# Thermal_imager_Down.net
KiCad netlist of a schematic drawn in Altium Designer
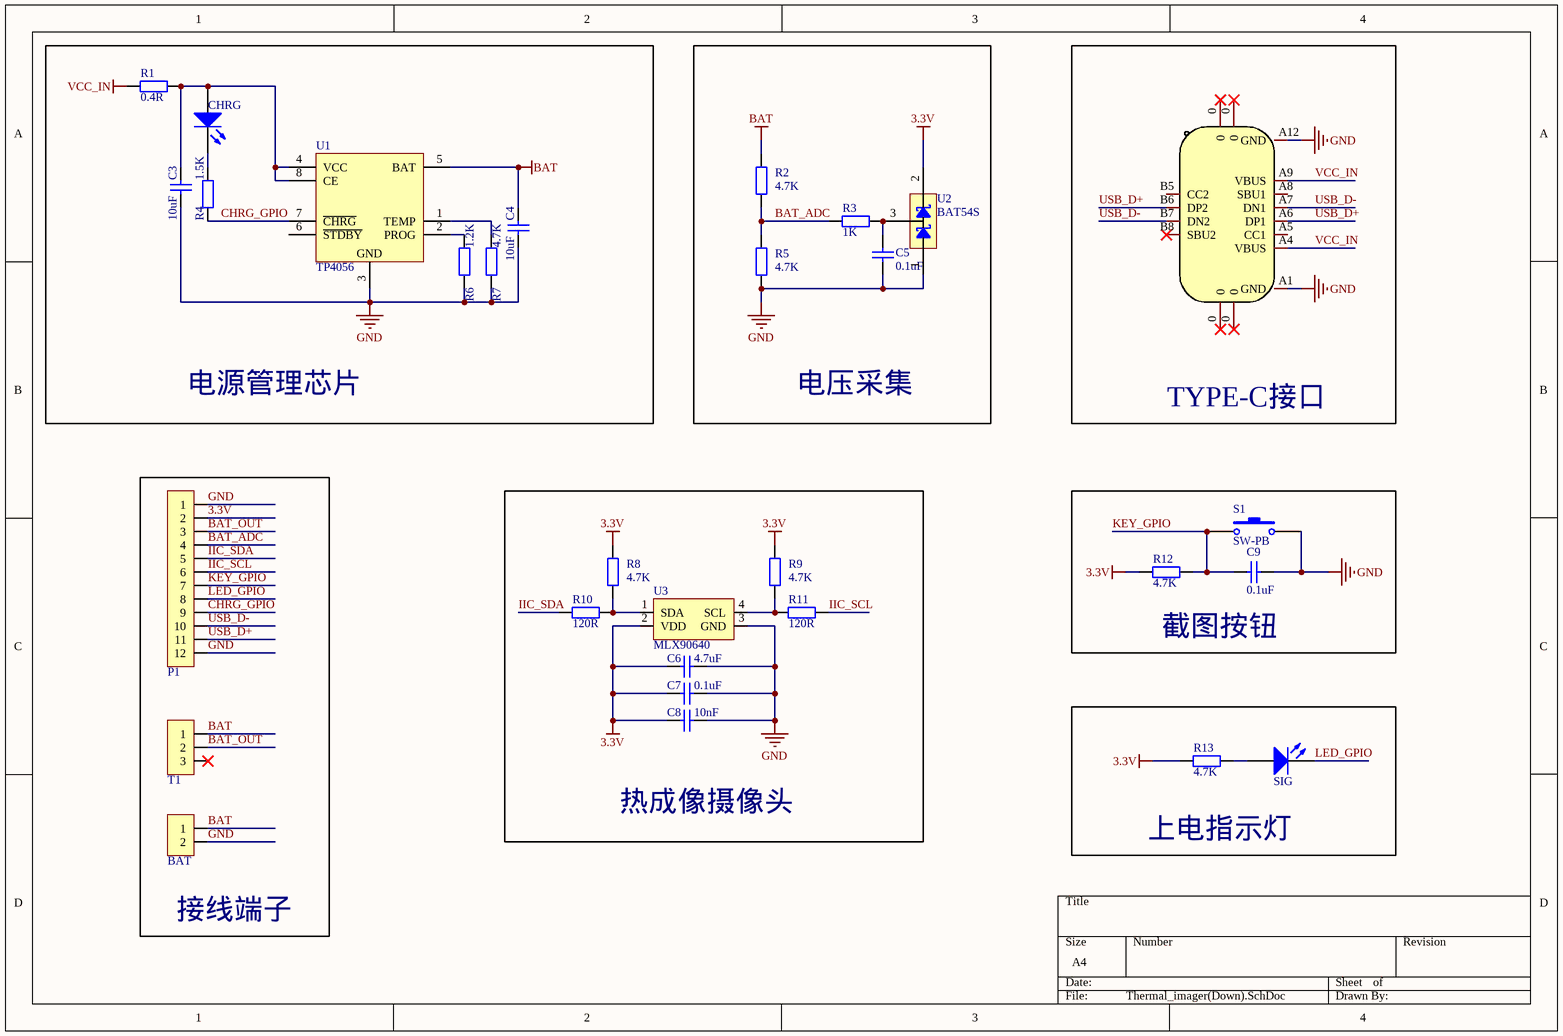
[diagram p0: Thermal_imager(Down).SchDoc]

(export (version "E")
  (design (tool "Eeschema 10.0.6"))
  (components
    (comp (ref "BAT")
      (value "Header 2*1")
      (footprint "COM_T_2.0_2P")
      (description "接插件")
      (fields (field (name "PUBLISHER") "Altium Limited"))
      (libsource (lib "Connect") (part "Header 2*1"))
    )
    (comp (ref "C3")
      (value "10uF")
      (footprint "LC-1206_C")
      (description "无极性电容")
      (fields (field (name "PUBLISHER") "Altium Limited"))
      (libsource (lib "Fszhang") (part "Cap"))
    )
    (comp (ref "C4")
      (value "10uF")
      (footprint "LC-1206_C")
      (description "无极性电容")
      (fields (field (name "PUBLISHER") "Altium Limited"))
      (libsource (lib "Fszhang") (part "Cap"))
    )
    (comp (ref "C5")
      (value "0.1uF")
      (footprint "LC-0603_C")
      (description "无极性电容")
      (fields (field (name "PUBLISHER") "Altium Limited"))
      (libsource (lib "Fszhang") (part "Cap"))
    )
    (comp (ref "C6")
      (value "4.7uF")
      (footprint "LC-0603_C")
      (description "无极性电容")
      (fields (field (name "PUBLISHER") "Altium Limited"))
      (libsource (lib "Fszhang") (part "Cap"))
    )
    (comp (ref "C7")
      (value "0.1uF")
      (footprint "LC-0603_C")
      (description "无极性电容")
      (fields (field (name "PUBLISHER") "Altium Limited"))
      (libsource (lib "Fszhang") (part "Cap"))
    )
    (comp (ref "C8")
      (value "10nF")
      (footprint "LC-0603_C")
      (description "无极性电容")
      (fields (field (name "PUBLISHER") "Altium Limited"))
      (libsource (lib "Fszhang") (part "Cap"))
    )
    (comp (ref "C9")
      (value "0.1uF")
      (footprint "LC-0603_C")
      (description "无极性电容")
      (fields (field (name "Comment") "Cap") (field (name "PUBLISHER") "Altium Limited"))
      (libsource (lib "Fszhang") (part "Cap"))
    )
    (comp (ref "CHRG")
      (value "LED0")
      (footprint "LC-0603_LED_S1")
      (description "发光二极管")
      (fields (field (name "PUBLISHER") "Altium Limited"))
      (libsource (lib "Fszhang") (part "LED0"))
    )
    (comp (ref "P1")
      (value "Header 12*1")
      (footprint "HDR12X1_A-1.27mm")
      (description "接插件")
      (fields (field (name "PUBLISHER") "Altium Limited"))
      (libsource (lib "Connect") (part "Header 12*1"))
    )
    (comp (ref "R1")
      (value "0.4R")
      (footprint "LC-1206_R")
      (description "贴片电阻")
      (fields (field (name "PUBLISHER") "Altium Limited"))
      (libsource (lib "") (part "=VALUE_1"))
    )
    (comp (ref "R2")
      (value "4.7K")
      (footprint "LC-0603_R")
      (description "贴片电阻")
      (fields (field (name "PUBLISHER") "Altium Limited"))
      (libsource (lib "Fszhang") (part "=VALUE"))
    )
    (comp (ref "R3")
      (value "1K")
      (footprint "LC-0603_R")
      (description "贴片电阻")
      (fields (field (name "PUBLISHER") "Altium Limited"))
      (libsource (lib "Fszhang") (part "Res1"))
    )
    (comp (ref "R4")
      (value "1.5K")
      (footprint "LC-0603_R")
      (description "贴片电阻")
      (fields (field (name "PUBLISHER") "Altium Limited"))
      (libsource (lib "Fszhang") (part "=VALUE"))
    )
    (comp (ref "R5")
      (value "4.7K")
      (footprint "LC-0603_R")
      (description "贴片电阻")
      (fields (field (name "PUBLISHER") "Altium Limited"))
      (libsource (lib "Fszhang") (part "=VALUE"))
    )
    (comp (ref "R6")
      (value "1.2K")
      (footprint "LC-0603_R")
      (description "贴片电阻")
      (fields (field (name "PUBLISHER") "Altium Limited"))
      (libsource (lib "Fszhang") (part "=VALUE"))
    )
    (comp (ref "R7")
      (value "4.7K")
      (footprint "LC-0603_R")
      (description "贴片电阻")
      (fields (field (name "PUBLISHER") "Altium Limited"))
      (libsource (lib "Fszhang") (part "=VALUE"))
    )
    (comp (ref "R8")
      (value "4.7K")
      (footprint "LC-0603_R")
      (description "贴片电阻")
      (fields (field (name "PUBLISHER") "Altium Limited"))
      (libsource (lib "Fszhang") (part "=VALUE"))
    )
    (comp (ref "R9")
      (value "4.7K")
      (footprint "LC-0603_R")
      (description "贴片电阻")
      (fields (field (name "PUBLISHER") "Altium Limited"))
      (libsource (lib "Fszhang") (part "=VALUE"))
    )
    (comp (ref "R10")
      (value "120R")
      (footprint "LC-0603_R")
      (description "贴片电阻")
      (fields (field (name "PUBLISHER") "Altium Limited"))
      (libsource (lib "") (part "=VALUE_2"))
    )
    (comp (ref "R11")
      (value "120R")
      (footprint "LC-0603_R")
      (description "贴片电阻")
      (fields (field (name "PUBLISHER") "Altium Limited"))
      (libsource (lib "") (part "=VALUE_2"))
    )
    (comp (ref "R12")
      (value "4.7K")
      (footprint "LC-0603_R")
      (description "贴片电阻")
      (fields (field (name "Comment") "Res1") (field (name "PUBLISHER") "Altium Limited"))
      (libsource (lib "Fszhang") (part "Res1"))
    )
    (comp (ref "R13")
      (value "4.7K")
      (footprint "LC-0603_R")
      (description "贴片电阻")
      (fields (field (name "Comment") "Res1") (field (name "PUBLISHER") "Altium Limited"))
      (libsource (lib "Fszhang") (part "Res1"))
    )
    (comp (ref "S1")
      (value "SW-PB")
      (footprint "KEY_3*6*3.5")
      (description "微动开关")
      (fields (field (name "PUBLISHER") "Altium Limited"))
      (libsource (lib "Fszhang") (part "SW-PB"))
    )
    (comp (ref "SIG")
      (value "LED0")
      (footprint "LC-0603_LED_S1")
      (description "发光二极管")
      (fields (field (name "PUBLISHER") "Altium Limited"))
      (libsource (lib "Fszhang") (part "LED0"))
    )
    (comp (ref "T1")
      (value "Header 3*1")
      (footprint "KEY_3*7")
      (description "接插件")
      (fields (field (name "PUBLISHER") "Altium Limited"))
      (libsource (lib "Connect") (part "Header 3*1"))
    )
    (comp (ref "U1")
      (value "TP4056")
      (footprint "ESOP_4056")
      (description "锂电池充电管理")
      (libsource (lib "Fszhang") (part "TP4056"))
    )
    (comp (ref "U2")
      (value "BAT54S")
      (footprint "SOT-23")
      (description "肖特基二极管")
      (libsource (lib "Fszhang") (part "BAT54S"))
    )
    (comp (ref "U3")
      (value "MLX90640")
      (footprint "MLX90640")
      (libsource (lib "Zfy_Library") (part "MLX90640"))
    )
    (comp (ref "USBC1")
      (value "TYPE-C")
      (footprint "TYPE-C-16P")
      (fields (field (name "MANUFACTURER") "精拓金") (field (name "MANUFACTURER PART") "918-418K2023S40001"))
      (libsource (lib "Zfy_Library") (part "TYPE-C"))
    )
  )
  (nets
    (net (code "1") (name "/BAT_ADC") (class "Default")
      (node (ref "P1") (pin "4") (pinfunction "4_4") (pintype "passive"))
      (node (ref "R2") (pin "2") (pinfunction "2_2") (pintype "passive"))
      (node (ref "R3") (pin "1") (pinfunction "1_1") (pintype "passive"))
      (node (ref "R5") (pin "1") (pinfunction "1_1") (pintype "passive"))
    )
    (net (code "2") (name "/BAT_OUT") (class "Default")
      (node (ref "P1") (pin "3") (pinfunction "3_3") (pintype "passive"))
      (node (ref "T1") (pin "2") (pinfunction "2_2") (pintype "passive"))
    )
    (net (code "3") (name "/CHRG_GPIO") (class "Default")
      (node (ref "P1") (pin "9") (pinfunction "9_9") (pintype "passive"))
      (node (ref "R4") (pin "2") (pinfunction "2_2") (pintype "passive"))
      (node (ref "U1") (pin "7") (pinfunction "~{CHRG}_7") (pintype "passive"))
    )
    (net (code "4") (name "/IIC_SCL") (class "Default")
      (node (ref "P1") (pin "6") (pinfunction "6_6") (pintype "passive"))
      (node (ref "R11") (pin "2") (pinfunction "2_2") (pintype "passive"))
    )
    (net (code "5") (name "/IIC_SDA") (class "Default")
      (node (ref "P1") (pin "5") (pinfunction "5_5") (pintype "passive"))
      (node (ref "R10") (pin "1") (pinfunction "1_1") (pintype "passive"))
    )
    (net (code "6") (name "/KEY_GPIO") (class "Default")
      (node (ref "C9") (pin "1") (pinfunction "1_1") (pintype "passive"))
      (node (ref "P1") (pin "7") (pinfunction "7_7") (pintype "passive"))
      (node (ref "R12") (pin "2") (pinfunction "2_2") (pintype "passive"))
      (node (ref "S1") (pin "1") (pinfunction "1_1") (pintype "passive"))
    )
    (net (code "7") (name "/LED_GPIO") (class "Default")
      (node (ref "P1") (pin "8") (pinfunction "8_8") (pintype "passive"))
      (node (ref "SIG") (pin "2") (pinfunction "K_2") (pintype "passive"))
    )
    (net (code "8") (name "/USB_D+") (class "Default")
      (node (ref "P1") (pin "11") (pinfunction "11_11") (pintype "passive"))
      (node (ref "USBC1") (pin "A6") (pinfunction "DP1_A6") (pintype "passive"))
      (node (ref "USBC1") (pin "B6") (pinfunction "DP2_B6") (pintype "passive"))
    )
    (net (code "9") (name "/USB_D-") (class "Default")
      (node (ref "P1") (pin "10") (pinfunction "10_10") (pintype "passive"))
      (node (ref "USBC1") (pin "A7") (pinfunction "DN1_A7") (pintype "passive"))
      (node (ref "USBC1") (pin "B7") (pinfunction "DN2_B7") (pintype "passive"))
    )
    (net (code "10") (name "3.3V") (class "Default")
      (node (ref "C6") (pin "2") (pinfunction "2_2") (pintype "passive"))
      (node (ref "C7") (pin "2") (pinfunction "2_2") (pintype "passive"))
      (node (ref "C8") (pin "2") (pinfunction "2_2") (pintype "passive"))
      (node (ref "P1") (pin "2") (pinfunction "2_2") (pintype "passive"))
      (node (ref "R12") (pin "1") (pinfunction "1_1") (pintype "passive"))
      (node (ref "R13") (pin "1") (pinfunction "1_1") (pintype "passive"))
      (node (ref "R8") (pin "1") (pinfunction "1_1") (pintype "passive"))
      (node (ref "R9") (pin "1") (pinfunction "1_1") (pintype "passive"))
      (node (ref "U2") (pin "2") (pinfunction "2_2") (pintype "passive"))
      (node (ref "U3") (pin "2") (pinfunction "VDD_2") (pintype "passive"))
    )
    (net (code "11") (name "BAT") (class "Default")
      (node (ref "BAT") (pin "1") (pinfunction "1_1") (pintype "passive"))
      (node (ref "C4") (pin "2") (pinfunction "2_2") (pintype "passive"))
      (node (ref "R2") (pin "1") (pinfunction "1_1") (pintype "passive"))
      (node (ref "T1") (pin "1") (pinfunction "1_1") (pintype "passive"))
      (node (ref "U1") (pin "5") (pinfunction "BAT_5") (pintype "passive"))
    )
    (net (code "12") (name "GND") (class "Default")
      (node (ref "BAT") (pin "2") (pinfunction "2_2") (pintype "passive"))
      (node (ref "C3") (pin "1") (pinfunction "1_1") (pintype "passive"))
      (node (ref "C4") (pin "1") (pinfunction "1_1") (pintype "passive"))
      (node (ref "C5") (pin "1") (pinfunction "1_1") (pintype "passive"))
      (node (ref "C6") (pin "1") (pinfunction "1_1") (pintype "passive"))
      (node (ref "C7") (pin "1") (pinfunction "1_1") (pintype "passive"))
      (node (ref "C8") (pin "1") (pinfunction "1_1") (pintype "passive"))
      (node (ref "C9") (pin "2") (pinfunction "2_2") (pintype "passive"))
      (node (ref "P1") (pin "1") (pinfunction "1_1") (pintype "passive"))
      (node (ref "P1") (pin "12") (pinfunction "12_12") (pintype "passive"))
      (node (ref "R5") (pin "2") (pinfunction "2_2") (pintype "passive"))
      (node (ref "R6") (pin "2") (pinfunction "2_2") (pintype "passive"))
      (node (ref "R7") (pin "2") (pinfunction "2_2") (pintype "passive"))
      (node (ref "S1") (pin "2") (pinfunction "2_2") (pintype "passive"))
      (node (ref "U1") (pin "3") (pinfunction "GND_3") (pintype "passive"))
      (node (ref "U2") (pin "1") (pinfunction "1_1") (pintype "passive"))
      (node (ref "U3") (pin "3") (pinfunction "GND_3") (pintype "passive"))
      (node (ref "USBC1") (pin "A1") (pinfunction "GND_A1") (pintype "passive"))
      (node (ref "USBC1") (pin "A12") (pinfunction "GND_A12") (pintype "passive"))
    )
    (net (code "13") (name "Net-(C5-Pad2)") (class "Default")
      (node (ref "C5") (pin "2") (pinfunction "2_2") (pintype "passive"))
      (node (ref "R3") (pin "2") (pinfunction "2_2") (pintype "passive"))
      (node (ref "U2") (pin "3") (pinfunction "3_3") (pintype "passive"))
    )
    (net (code "14") (name "Net-(CHRG-A)") (class "Default")
      (node (ref "C3") (pin "2") (pinfunction "2_2") (pintype "passive"))
      (node (ref "CHRG") (pin "1") (pinfunction "A_1") (pintype "passive"))
      (node (ref "R1") (pin "1") (pinfunction "1_1") (pintype "passive"))
      (node (ref "U1") (pin "4") (pinfunction "VCC_4") (pintype "passive"))
      (node (ref "U1") (pin "8") (pinfunction "CE_8") (pintype "passive"))
    )
    (net (code "15") (name "Net-(CHRG-K)") (class "Default")
      (node (ref "CHRG") (pin "2") (pinfunction "K_2") (pintype "passive"))
      (node (ref "R4") (pin "1") (pinfunction "1_1") (pintype "passive"))
    )
    (net (code "16") (name "Net-(SIG-A)") (class "Default")
      (node (ref "R13") (pin "2") (pinfunction "2_2") (pintype "passive"))
      (node (ref "SIG") (pin "1") (pinfunction "A_1") (pintype "passive"))
    )
    (net (code "17") (name "Net-(U1-PROG)") (class "Default")
      (node (ref "R6") (pin "1") (pinfunction "1_1") (pintype "passive"))
      (node (ref "U1") (pin "2") (pinfunction "PROG_2") (pintype "passive"))
    )
    (net (code "18") (name "Net-(U1-TEMP)") (class "Default")
      (node (ref "R7") (pin "1") (pinfunction "1_1") (pintype "passive"))
      (node (ref "U1") (pin "1") (pinfunction "TEMP_1") (pintype "passive"))
    )
    (net (code "19") (name "Net-(U3-SCL)") (class "Default")
      (node (ref "R11") (pin "1") (pinfunction "1_1") (pintype "passive"))
      (node (ref "R9") (pin "2") (pinfunction "2_2") (pintype "passive"))
      (node (ref "U3") (pin "4") (pinfunction "SCL_4") (pintype "passive"))
    )
    (net (code "20") (name "Net-(U3-SDA)") (class "Default")
      (node (ref "R10") (pin "2") (pinfunction "2_2") (pintype "passive"))
      (node (ref "R8") (pin "2") (pinfunction "2_2") (pintype "passive"))
      (node (ref "U3") (pin "1") (pinfunction "SDA_1") (pintype "passive"))
    )
    (net (code "21") (name "VCC_IN") (class "Default")
      (node (ref "R1") (pin "2") (pinfunction "2_2") (pintype "passive"))
      (node (ref "USBC1") (pin "A4") (pinfunction "VBUS_A4") (pintype "passive"))
      (node (ref "USBC1") (pin "A9") (pinfunction "VBUS_A9") (pintype "passive"))
    )
    (net (code "22") (name "unconnected-(T1-Pad3)") (class "Default")
      (node (ref "T1") (pin "3") (pinfunction "3_3") (pintype "passive+no_connect"))
    )
    (net (code "23") (name "unconnected-(U1-~{STDBY}-Pad6)") (class "Default")
      (node (ref "U1") (pin "6") (pinfunction "~{STDBY}_6") (pintype "passive"))
    )
    (net (code "24") (name "unconnected-(USBC1-CC1-PadA5)") (class "Default")
      (node (ref "USBC1") (pin "A5") (pinfunction "CC1_A5") (pintype "passive"))
    )
    (net (code "25") (name "unconnected-(USBC1-CC2-PadB5)") (class "Default")
      (node (ref "USBC1") (pin "B5") (pinfunction "CC2_B5") (pintype "passive"))
    )
    (net (code "26") (name "unconnected-(USBC1-Pad0)") (class "Default")
      (node (ref "USBC1") (pin "0") (pinfunction "0_0") (pintype "passive+no_connect"))
    )
    (net (code "27") (name "unconnected-(USBC1-Pad0)_1") (class "Default")
      (node (ref "USBC1") (pin "0") (pinfunction "0_0") (pintype "passive+no_connect"))
    )
    (net (code "28") (name "unconnected-(USBC1-Pad0)_2") (class "Default")
      (node (ref "USBC1") (pin "0") (pinfunction "0_0") (pintype "passive+no_connect"))
    )
    (net (code "29") (name "unconnected-(USBC1-Pad0)_3") (class "Default")
      (node (ref "USBC1") (pin "0") (pinfunction "0_0") (pintype "passive+no_connect"))
    )
    (net (code "30") (name "unconnected-(USBC1-SBU1-PadA8)") (class "Default")
      (node (ref "USBC1") (pin "A8") (pinfunction "SBU1_A8") (pintype "passive"))
    )
    (net (code "31") (name "unconnected-(USBC1-SBU2-PadB8)") (class "Default")
      (node (ref "USBC1") (pin "B8") (pinfunction "SBU2_B8") (pintype "passive+no_connect"))
    )
  )
)
